# DRV8701ESheet.net
KiCad netlist of a schematic drawn in Altium Designer
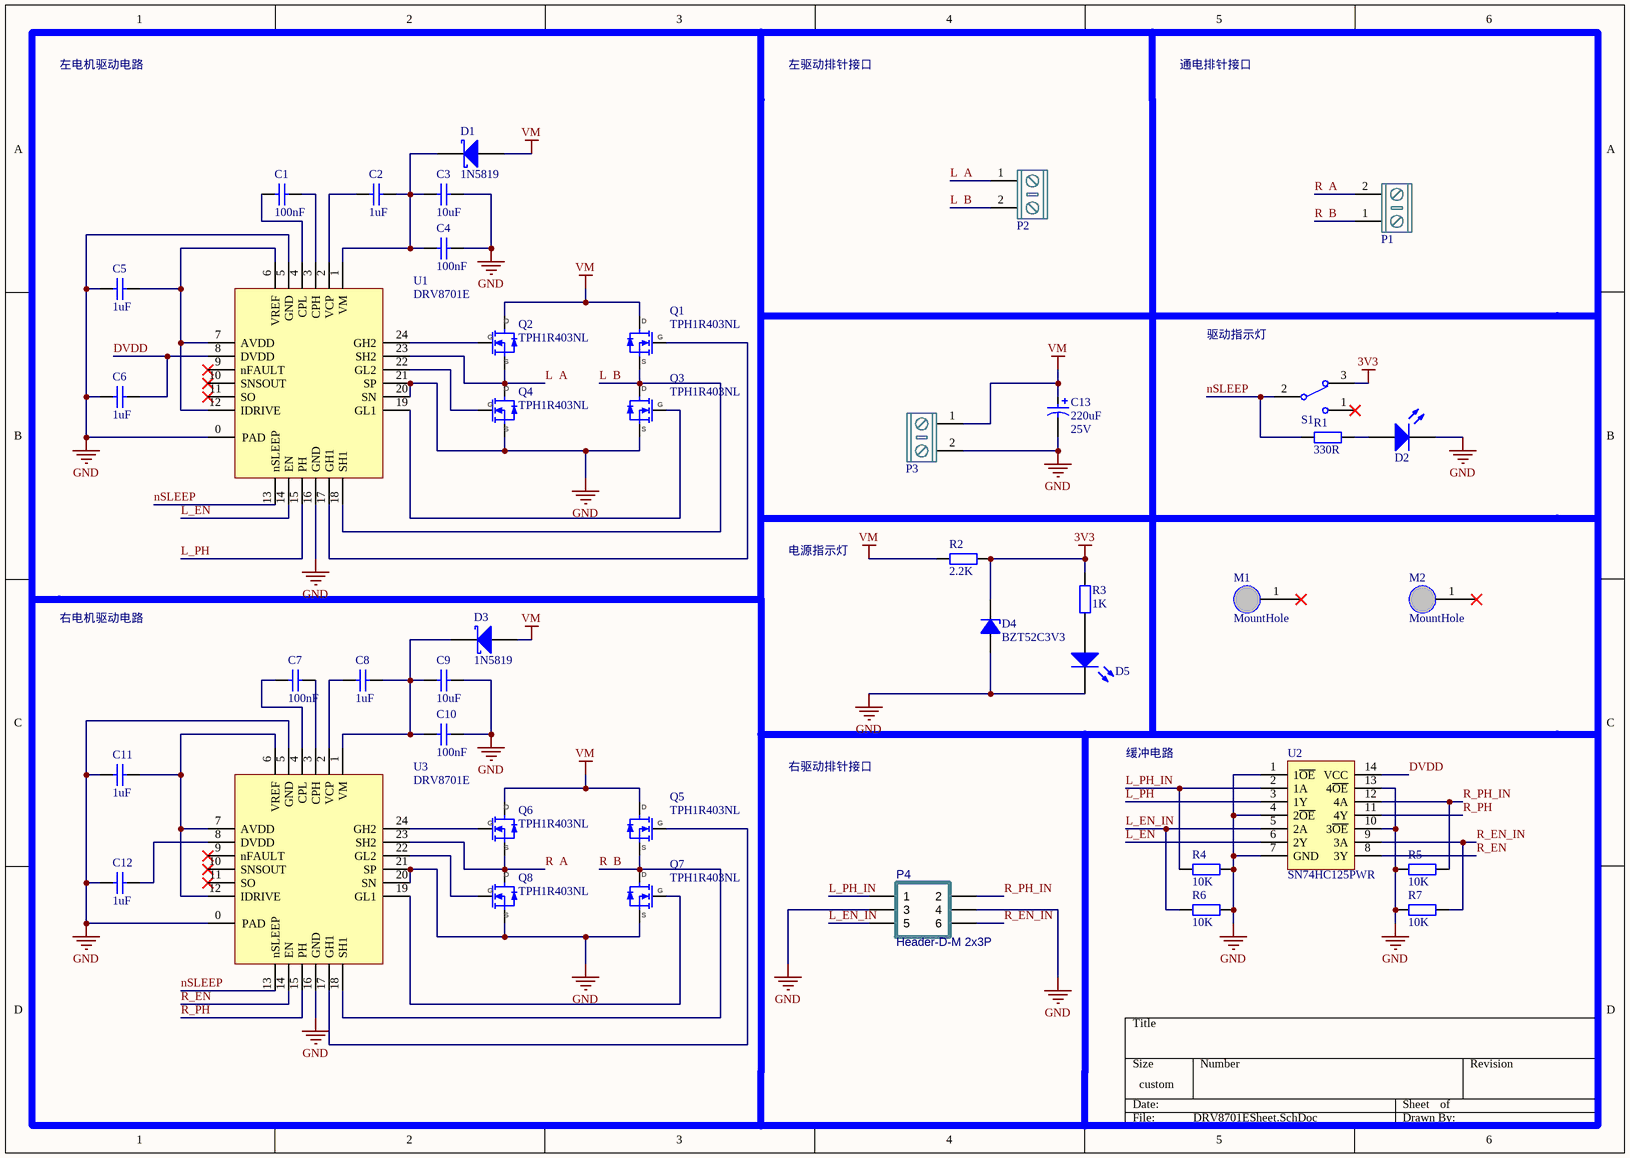
[diagram p0: DRV8701ESheet.SchDoc]

(export (version "E")
  (design (tool "Eeschema 10.0.6"))
  (components
    (comp (ref "C1")
      (value "100nF")
      (footprint "C0603_L")
      (description "贴片电容")
      (libsource (lib "0.1_电容&电感&电阻&保险丝") (part "C-SMD"))
    )
    (comp (ref "C2")
      (value "1uF")
      (footprint "C0603_L")
      (description "贴片电容")
      (libsource (lib "0.1_电容&电感&电阻&保险丝") (part "C-SMD"))
    )
    (comp (ref "C3")
      (value "10uF")
      (footprint "C0603_L")
      (description "贴片电容")
      (libsource (lib "0.1_电容&电感&电阻&保险丝") (part "C-SMD"))
    )
    (comp (ref "C4")
      (value "100nF")
      (footprint "C0603_L")
      (description "贴片电容")
      (libsource (lib "0.1_电容&电感&电阻&保险丝") (part "C-SMD"))
    )
    (comp (ref "C5")
      (value "1uF")
      (footprint "C0603_L")
      (description "贴片电容")
      (libsource (lib "0.1_电容&电感&电阻&保险丝") (part "C-SMD"))
    )
    (comp (ref "C6")
      (value "1uF")
      (footprint "C0603_L")
      (description "贴片电容")
      (libsource (lib "0.1_电容&电感&电阻&保险丝") (part "C-SMD"))
    )
    (comp (ref "C7")
      (value "100nF")
      (footprint "C0603_L")
      (description "贴片电容")
      (libsource (lib "0.1_电容&电感&电阻&保险丝") (part "C-SMD"))
    )
    (comp (ref "C8")
      (value "1uF")
      (footprint "C0603_L")
      (description "贴片电容")
      (libsource (lib "0.1_电容&电感&电阻&保险丝") (part "C-SMD"))
    )
    (comp (ref "C9")
      (value "10uF")
      (footprint "C0603_L")
      (description "贴片电容")
      (libsource (lib "0.1_电容&电感&电阻&保险丝") (part "C-SMD"))
    )
    (comp (ref "C10")
      (value "100nF")
      (footprint "C0603_L")
      (description "贴片电容")
      (libsource (lib "0.1_电容&电感&电阻&保险丝") (part "C-SMD"))
    )
    (comp (ref "C11")
      (value "1uF")
      (footprint "C0603_L")
      (description "贴片电容")
      (libsource (lib "0.1_电容&电感&电阻&保险丝") (part "C-SMD"))
    )
    (comp (ref "C12")
      (value "1uF")
      (footprint "C0603_L")
      (description "贴片电容")
      (libsource (lib "0.1_电容&电感&电阻&保险丝") (part "C-SMD"))
    )
    (comp (ref "C13")
      (value "220uF")
      (footprint "CAPPR3.5-8X11.5")
      (description "Polarized Capacitor (Radial)")
      (fields
        (field (name "VOLTAGE") "25V")
        (field (name "Comment") "220uF 25V")
        (field (name "PUBLISHER") "Altium Limited")
      )
      (libsource (lib "DRV8701E 双驱V1.1 集成封装库") (part "Cap-Elect"))
    )
    (comp (ref "D1")
      (value "1N5819")
      (footprint "SOD-323")
      (description "肖特基二极管")
      (libsource (lib "0.2_二极管&整流桥") (part "1N5819"))
    )
    (comp (ref "D2")
      (value "LED")
      (footprint "LED-0603_R")
      (description "贴片发光二极管")
      (libsource (lib "0.3_LED发光二极管") (part "LED_SMD"))
    )
    (comp (ref "D3")
      (value "1N5819")
      (footprint "SOD-323")
      (description "肖特基二极管")
      (libsource (lib "0.2_二极管&整流桥") (part "1N5819"))
    )
    (comp (ref "D4")
      (value "BZT52C3V3")
      (footprint "SOD-123-L")
      (description "3.3V稳压二极管")
      (fields (field (name "PUBLISHER") "Altium Limited"))
      (libsource (lib "智能车驱动板DRV8701E") (part "Diode Zen"))
    )
    (comp (ref "D5")
      (value "LED")
      (footprint "LED-0603_R")
      (description "贴片发光二极管")
      (libsource (lib "智能车驱动板DRV8701E") (part "LED_SMD"))
    )
    (comp (ref "M1")
      (value "MountHole")
      (footprint "M3-MountSlot")
      (description "固定孔")
      (libsource (lib "DRV8701E 双驱V1.1 集成封装库") (part "MountHole"))
    )
    (comp (ref "M2")
      (value "MountHole")
      (footprint "M3-MountSlot")
      (description "固定孔")
      (libsource (lib "DRV8701E 双驱V1.1 集成封装库") (part "MountHole"))
    )
    (comp (ref "P1")
      (value "KF/WJ/DG 30x connecter")
      (footprint "XT30-M")
      (description "接线端子 2Pin")
      (libsource (lib "RT1064_V1主板器件封装集成库") (part "KF/WJ/DG 30x"))
    )
    (comp (ref "P2")
      (value "KF/WJ/DG 30x connecter")
      (footprint "XT30-M")
      (description "接线端子 2Pin")
      (libsource (lib "RT1064_V1主板器件封装集成库") (part "KF/WJ/DG 30x"))
    )
    (comp (ref "P3")
      (value "KF/WJ/DG 30x connecter")
      (footprint "KF/WJ/DG 301-2p-5.0mm")
      (description "接线端子 2Pin")
      (libsource (lib "RT1064_V1主板器件封装集成库") (part "KF/WJ/DG 30x"))
    )
    (comp (ref "P4")
      (value "Header-D-M 2x3P")
      (footprint "HDR2X3-M-SMT")
      (description "2x3pin, 贴片, 双排针")
      (libsource (lib "RT1064_V1主板器件封装集成库") (part "Header-S-M 2x3P"))
    )
    (comp (ref "Q1")
      (value "TPH1R403NL")
      (footprint "DFN5x6")
      (description "N沟道MOS")
      (libsource (lib "0.4_场效应管&可控硅") (part "TPH1R403NL"))
    )
    (comp (ref "Q2")
      (value "TPH1R403NL")
      (footprint "DFN5x6")
      (description "N沟道MOS")
      (libsource (lib "0.4_场效应管&可控硅") (part "TPH1R403NL"))
    )
    (comp (ref "Q3")
      (value "TPH1R403NL")
      (footprint "DFN5x6")
      (description "N沟道MOS")
      (libsource (lib "0.4_场效应管&可控硅") (part "TPH1R403NL"))
    )
    (comp (ref "Q4")
      (value "TPH1R403NL")
      (footprint "DFN5x6")
      (description "N沟道MOS")
      (libsource (lib "0.4_场效应管&可控硅") (part "TPH1R403NL"))
    )
    (comp (ref "Q5")
      (value "TPH1R403NL")
      (footprint "DFN5x6")
      (description "N沟道MOS")
      (libsource (lib "0.4_场效应管&可控硅") (part "TPH1R403NL"))
    )
    (comp (ref "Q6")
      (value "TPH1R403NL")
      (footprint "DFN5x6")
      (description "N沟道MOS")
      (libsource (lib "0.4_场效应管&可控硅") (part "TPH1R403NL"))
    )
    (comp (ref "Q7")
      (value "TPH1R403NL")
      (footprint "DFN5x6")
      (description "N沟道MOS")
      (libsource (lib "0.4_场效应管&可控硅") (part "TPH1R403NL"))
    )
    (comp (ref "Q8")
      (value "TPH1R403NL")
      (footprint "DFN5x6")
      (description "N沟道MOS")
      (libsource (lib "0.4_场效应管&可控硅") (part "TPH1R403NL"))
    )
    (comp (ref "R1")
      (value "330R")
      (footprint "R0603_L")
      (description "贴片电阻")
      (libsource (lib "0.1_电容&电感&电阻&保险丝") (part "R-SMD"))
    )
    (comp (ref "R2")
      (value "2.2K")
      (footprint "R0603_L")
      (description "贴片电阻")
      (libsource (lib "0.1_电容&电感&电阻&保险丝") (part "R-SMD"))
    )
    (comp (ref "R3")
      (value "1K")
      (footprint "R0603_L")
      (description "贴片电阻")
      (libsource (lib "智能车驱动板DRV8701E") (part "R-SMD"))
    )
    (comp (ref "R4")
      (value "10K")
      (footprint "R0603_L")
      (description "贴片电阻")
      (libsource (lib "0.1_电容&电感&电阻&保险丝") (part "R-SMD"))
    )
    (comp (ref "R5")
      (value "10K")
      (footprint "R0603_L")
      (description "贴片电阻")
      (libsource (lib "0.1_电容&电感&电阻&保险丝") (part "R-SMD"))
    )
    (comp (ref "R6")
      (value "10K")
      (footprint "R0603_L")
      (description "贴片电阻")
      (libsource (lib "0.1_电容&电感&电阻&保险丝") (part "R-SMD"))
    )
    (comp (ref "R7")
      (value "10K")
      (footprint "R0603_L")
      (description "贴片电阻")
      (libsource (lib "0.1_电容&电感&电阻&保险丝") (part "R-SMD"))
    )
    (comp (ref "S1")
      (value "SW-SPDT")
      (footprint "SS-12F23")
      (description "单刀双掷开关 3脚船型、钮子、拨动开关 SPDT Subminiature Toggle Switch")
      (fields (field (name "PUBLISHER") "Altium Limited"))
      (libsource (lib "RT1064_V1主板器件封装集成库") (part "SW-SPDT"))
    )
    (comp (ref "U1")
      (value "DRV8701E")
      (footprint "QFN24-4x4")
      (description "DRV8701E Ti全桥驱动芯片")
      (libsource (lib "智能车驱动板DRV8701E") (part "DRV8701E"))
    )
    (comp (ref "U2")
      (value "SN74HC125PWR")
      (footprint "TSSOP14")
      (description "三态输出的四路缓冲器")
      (libsource (lib "智能车驱动板DRV8701E") (part "SN74HC125PWR"))
    )
    (comp (ref "U3")
      (value "DRV8701E")
      (footprint "QFN24-4x4")
      (description "DRV8701E Ti全桥驱动芯片")
      (libsource (lib "智能车驱动板DRV8701E") (part "DRV8701E"))
    )
  )
  (nets
    (net (code "1") (name "/DVDD") (class "Default")
      (node (ref "C6") (pin "2") (pinfunction "2_2") (pintype "passive"))
      (node (ref "U1") (pin "8") (pinfunction "DVDD_8") (pintype "passive"))
      (node (ref "U2") (pin "14") (pinfunction "VCC_14") (pintype "passive"))
    )
    (net (code "2") (name "/L  A") (class "Default")
      (node (ref "P2") (pin "1") (pinfunction "1_1") (pintype "passive"))
      (node (ref "Q2") (pin "3") (pinfunction "S_3") (pintype "passive"))
      (node (ref "Q4") (pin "1") (pinfunction "D_1") (pintype "passive"))
      (node (ref "U1") (pin "23") (pinfunction "SH2_23") (pintype "passive"))
    )
    (net (code "3") (name "/L  B") (class "Default")
      (node (ref "P2") (pin "2") (pinfunction "2_2") (pintype "passive"))
      (node (ref "Q1") (pin "3") (pinfunction "S_3") (pintype "passive"))
      (node (ref "Q3") (pin "1") (pinfunction "D_1") (pintype "passive"))
      (node (ref "U1") (pin "18") (pinfunction "SH1_18") (pintype "passive"))
    )
    (net (code "4") (name "/L_EN") (class "Default")
      (node (ref "U1") (pin "14") (pinfunction "EN_14") (pintype "passive"))
      (node (ref "U2") (pin "6") (pinfunction "2Y_6") (pintype "passive"))
    )
    (net (code "5") (name "/L_EN_IN") (class "Default")
      (node (ref "P4") (pin "5") (pinfunction "5_5") (pintype "passive"))
      (node (ref "R6") (pin "1") (pinfunction "1_1") (pintype "passive"))
      (node (ref "U2") (pin "5") (pinfunction "2A_5") (pintype "passive"))
    )
    (net (code "6") (name "/L_PH") (class "Default")
      (node (ref "U1") (pin "15") (pinfunction "PH_15") (pintype "passive"))
      (node (ref "U2") (pin "3") (pinfunction "1Y_3") (pintype "passive"))
    )
    (net (code "7") (name "/L_PH_IN") (class "Default")
      (node (ref "P4") (pin "1") (pinfunction "1_1") (pintype "passive"))
      (node (ref "R4") (pin "1") (pinfunction "1_1") (pintype "passive"))
      (node (ref "U2") (pin "2") (pinfunction "1A_2") (pintype "passive"))
    )
    (net (code "8") (name "/R  A") (class "Default")
      (node (ref "P1") (pin "2") (pinfunction "2_2") (pintype "passive"))
      (node (ref "Q6") (pin "3") (pinfunction "S_3") (pintype "passive"))
      (node (ref "Q8") (pin "1") (pinfunction "D_1") (pintype "passive"))
      (node (ref "U3") (pin "23") (pinfunction "SH2_23") (pintype "passive"))
    )
    (net (code "9") (name "/R  B") (class "Default")
      (node (ref "P1") (pin "1") (pinfunction "1_1") (pintype "passive"))
      (node (ref "Q5") (pin "3") (pinfunction "S_3") (pintype "passive"))
      (node (ref "Q7") (pin "1") (pinfunction "D_1") (pintype "passive"))
      (node (ref "U3") (pin "18") (pinfunction "SH1_18") (pintype "passive"))
    )
    (net (code "10") (name "/R_EN") (class "Default")
      (node (ref "U2") (pin "8") (pinfunction "3Y_8") (pintype "passive"))
      (node (ref "U3") (pin "14") (pinfunction "EN_14") (pintype "passive"))
    )
    (net (code "11") (name "/R_EN_IN") (class "Default")
      (node (ref "P4") (pin "6") (pinfunction "6_6") (pintype "passive"))
      (node (ref "R7") (pin "2") (pinfunction "2_2") (pintype "passive"))
      (node (ref "U2") (pin "9") (pinfunction "3A_9") (pintype "passive"))
    )
    (net (code "12") (name "/R_PH") (class "Default")
      (node (ref "U2") (pin "11") (pinfunction "4Y_11") (pintype "passive"))
      (node (ref "U3") (pin "15") (pinfunction "PH_15") (pintype "passive"))
    )
    (net (code "13") (name "/R_PH_IN") (class "Default")
      (node (ref "P4") (pin "2") (pinfunction "2_2") (pintype "passive"))
      (node (ref "R5") (pin "2") (pinfunction "2_2") (pintype "passive"))
      (node (ref "U2") (pin "12") (pinfunction "4A_12") (pintype "passive"))
    )
    (net (code "14") (name "/nSLEEP") (class "Default")
      (node (ref "R1") (pin "1") (pinfunction "1_1") (pintype "passive"))
      (node (ref "S1") (pin "2") (pintype "passive"))
      (node (ref "U1") (pin "13") (pinfunction "nSLEEP_13") (pintype "passive"))
      (node (ref "U3") (pin "13") (pinfunction "nSLEEP_13") (pintype "passive"))
    )
    (net (code "15") (name "3V3") (class "Default")
      (node (ref "D4") (pin "K") (pinfunction "K_K") (pintype "passive"))
      (node (ref "R2") (pin "2") (pinfunction "2_2") (pintype "passive"))
      (node (ref "R3") (pin "2") (pinfunction "2_2") (pintype "passive"))
      (node (ref "S1") (pin "3") (pintype "passive"))
    )
    (net (code "16") (name "GND") (class "Default")
      (node (ref "C10") (pin "2") (pinfunction "2_2") (pintype "passive"))
      (node (ref "C11") (pin "1") (pinfunction "1_1") (pintype "passive"))
      (node (ref "C12") (pin "1") (pinfunction "1_1") (pintype "passive"))
      (node (ref "C13") (pin "2") (pinfunction "2_2") (pintype "passive"))
      (node (ref "C3") (pin "2") (pinfunction "2_2") (pintype "passive"))
      (node (ref "C4") (pin "2") (pinfunction "2_2") (pintype "passive"))
      (node (ref "C5") (pin "1") (pinfunction "1_1") (pintype "passive"))
      (node (ref "C6") (pin "1") (pinfunction "1_1") (pintype "passive"))
      (node (ref "C9") (pin "2") (pinfunction "2_2") (pintype "passive"))
      (node (ref "D2") (pin "2") (pinfunction "K_2") (pintype "passive"))
      (node (ref "D4") (pin "A") (pinfunction "A_A") (pintype "passive"))
      (node (ref "D5") (pin "2") (pinfunction "K_2") (pintype "passive"))
      (node (ref "P3") (pin "2") (pinfunction "2_2") (pintype "passive"))
      (node (ref "P4") (pin "3") (pinfunction "3_3") (pintype "passive"))
      (node (ref "P4") (pin "4") (pinfunction "4_4") (pintype "passive"))
      (node (ref "Q3") (pin "3") (pinfunction "S_3") (pintype "passive"))
      (node (ref "Q4") (pin "3") (pinfunction "S_3") (pintype "passive"))
      (node (ref "Q7") (pin "3") (pinfunction "S_3") (pintype "passive"))
      (node (ref "Q8") (pin "3") (pinfunction "S_3") (pintype "passive"))
      (node (ref "R4") (pin "2") (pinfunction "2_2") (pintype "passive"))
      (node (ref "R5") (pin "1") (pinfunction "1_1") (pintype "passive"))
      (node (ref "R6") (pin "2") (pinfunction "2_2") (pintype "passive"))
      (node (ref "R7") (pin "1") (pinfunction "1_1") (pintype "passive"))
      (node (ref "U1") (pin "0") (pinfunction "PAD_0") (pintype "passive"))
      (node (ref "U1") (pin "16") (pinfunction "GND_16") (pintype "passive"))
      (node (ref "U1") (pin "20") (pinfunction "SN_20") (pintype "passive"))
      (node (ref "U1") (pin "21") (pinfunction "SP_21") (pintype "passive"))
      (node (ref "U1") (pin "5") (pinfunction "GND_5") (pintype "passive"))
      (node (ref "U2") (pin "1") (pinfunction "1~{OE}_1") (pintype "passive"))
      (node (ref "U2") (pin "10") (pinfunction "3~{OE}_10") (pintype "passive"))
      (node (ref "U2") (pin "13") (pinfunction "4~{OE}_13") (pintype "passive"))
      (node (ref "U2") (pin "4") (pinfunction "2~{OE}_4") (pintype "passive"))
      (node (ref "U2") (pin "7") (pinfunction "GND_7") (pintype "passive"))
      (node (ref "U3") (pin "0") (pinfunction "PAD_0") (pintype "passive"))
      (node (ref "U3") (pin "16") (pinfunction "GND_16") (pintype "passive"))
      (node (ref "U3") (pin "20") (pinfunction "SN_20") (pintype "passive"))
      (node (ref "U3") (pin "21") (pinfunction "SP_21") (pintype "passive"))
      (node (ref "U3") (pin "5") (pinfunction "GND_5") (pintype "passive"))
    )
    (net (code "17") (name "Net-(D1-K)") (class "Default")
      (node (ref "C2") (pin "2") (pinfunction "2_2") (pintype "passive"))
      (node (ref "C3") (pin "1") (pinfunction "1_1") (pintype "passive"))
      (node (ref "C4") (pin "1") (pinfunction "1_1") (pintype "passive"))
      (node (ref "D1") (pin "2") (pinfunction "K_2") (pintype "passive"))
      (node (ref "U1") (pin "1") (pinfunction "VM_1") (pintype "passive"))
    )
    (net (code "18") (name "Net-(D2-A)") (class "Default")
      (node (ref "D2") (pin "1") (pinfunction "A_1") (pintype "passive"))
      (node (ref "R1") (pin "2") (pinfunction "2_2") (pintype "passive"))
    )
    (net (code "19") (name "Net-(D3-K)") (class "Default")
      (node (ref "C10") (pin "1") (pinfunction "1_1") (pintype "passive"))
      (node (ref "C8") (pin "2") (pinfunction "2_2") (pintype "passive"))
      (node (ref "C9") (pin "1") (pinfunction "1_1") (pintype "passive"))
      (node (ref "D3") (pin "2") (pinfunction "K_2") (pintype "passive"))
      (node (ref "U3") (pin "1") (pinfunction "VM_1") (pintype "passive"))
    )
    (net (code "20") (name "Net-(D5-A)") (class "Default")
      (node (ref "D5") (pin "1") (pinfunction "A_1") (pintype "passive"))
      (node (ref "R3") (pin "1") (pinfunction "1_1") (pintype "passive"))
    )
    (net (code "21") (name "Net-(Q1-G)") (class "Default")
      (node (ref "Q1") (pin "2") (pinfunction "G_2") (pintype "passive"))
      (node (ref "U1") (pin "17") (pinfunction "GH1_17") (pintype "passive"))
    )
    (net (code "22") (name "Net-(Q2-G)") (class "Default")
      (node (ref "Q2") (pin "2") (pinfunction "G_2") (pintype "passive"))
      (node (ref "U1") (pin "24") (pinfunction "GH2_24") (pintype "passive"))
    )
    (net (code "23") (name "Net-(Q3-G)") (class "Default")
      (node (ref "Q3") (pin "2") (pinfunction "G_2") (pintype "passive"))
      (node (ref "U1") (pin "19") (pinfunction "GL1_19") (pintype "passive"))
    )
    (net (code "24") (name "Net-(Q4-G)") (class "Default")
      (node (ref "Q4") (pin "2") (pinfunction "G_2") (pintype "passive"))
      (node (ref "U1") (pin "22") (pinfunction "GL2_22") (pintype "passive"))
    )
    (net (code "25") (name "Net-(Q5-G)") (class "Default")
      (node (ref "Q5") (pin "2") (pinfunction "G_2") (pintype "passive"))
      (node (ref "U3") (pin "17") (pinfunction "GH1_17") (pintype "passive"))
    )
    (net (code "26") (name "Net-(Q6-G)") (class "Default")
      (node (ref "Q6") (pin "2") (pinfunction "G_2") (pintype "passive"))
      (node (ref "U3") (pin "24") (pinfunction "GH2_24") (pintype "passive"))
    )
    (net (code "27") (name "Net-(Q7-G)") (class "Default")
      (node (ref "Q7") (pin "2") (pinfunction "G_2") (pintype "passive"))
      (node (ref "U3") (pin "19") (pinfunction "GL1_19") (pintype "passive"))
    )
    (net (code "28") (name "Net-(Q8-G)") (class "Default")
      (node (ref "Q8") (pin "2") (pinfunction "G_2") (pintype "passive"))
      (node (ref "U3") (pin "22") (pinfunction "GL2_22") (pintype "passive"))
    )
    (net (code "29") (name "Net-(U1-AVDD)") (class "Default")
      (node (ref "C5") (pin "2") (pinfunction "2_2") (pintype "passive"))
      (node (ref "U1") (pin "12") (pinfunction "IDRIVE_12") (pintype "passive"))
      (node (ref "U1") (pin "6") (pinfunction "VREF_6") (pintype "passive"))
      (node (ref "U1") (pin "7") (pinfunction "AVDD_7") (pintype "passive"))
    )
    (net (code "30") (name "Net-(U1-CPH)") (class "Default")
      (node (ref "C1") (pin "2") (pinfunction "2_2") (pintype "passive"))
      (node (ref "U1") (pin "3") (pinfunction "CPH_3") (pintype "passive"))
    )
    (net (code "31") (name "Net-(U1-CPL)") (class "Default")
      (node (ref "C1") (pin "1") (pinfunction "1_1") (pintype "passive"))
      (node (ref "U1") (pin "4") (pinfunction "CPL_4") (pintype "passive"))
    )
    (net (code "32") (name "Net-(U1-VCP)") (class "Default")
      (node (ref "C2") (pin "1") (pinfunction "1_1") (pintype "passive"))
      (node (ref "U1") (pin "2") (pinfunction "VCP_2") (pintype "passive"))
    )
    (net (code "33") (name "Net-(U3-AVDD)") (class "Default")
      (node (ref "C11") (pin "2") (pinfunction "2_2") (pintype "passive"))
      (node (ref "U3") (pin "12") (pinfunction "IDRIVE_12") (pintype "passive"))
      (node (ref "U3") (pin "6") (pinfunction "VREF_6") (pintype "passive"))
      (node (ref "U3") (pin "7") (pinfunction "AVDD_7") (pintype "passive"))
    )
    (net (code "34") (name "Net-(U3-CPH)") (class "Default")
      (node (ref "C7") (pin "2") (pinfunction "2_2") (pintype "passive"))
      (node (ref "U3") (pin "3") (pinfunction "CPH_3") (pintype "passive"))
    )
    (net (code "35") (name "Net-(U3-CPL)") (class "Default")
      (node (ref "C7") (pin "1") (pinfunction "1_1") (pintype "passive"))
      (node (ref "U3") (pin "4") (pinfunction "CPL_4") (pintype "passive"))
    )
    (net (code "36") (name "Net-(U3-DVDD)") (class "Default")
      (node (ref "C12") (pin "2") (pinfunction "2_2") (pintype "passive"))
      (node (ref "U3") (pin "8") (pinfunction "DVDD_8") (pintype "passive"))
    )
    (net (code "37") (name "Net-(U3-VCP)") (class "Default")
      (node (ref "C8") (pin "1") (pinfunction "1_1") (pintype "passive"))
      (node (ref "U3") (pin "2") (pinfunction "VCP_2") (pintype "passive"))
    )
    (net (code "38") (name "VM") (class "Default")
      (node (ref "C13") (pin "1") (pinfunction "1_1") (pintype "passive"))
      (node (ref "D1") (pin "1") (pinfunction "A_1") (pintype "passive"))
      (node (ref "D3") (pin "1") (pinfunction "A_1") (pintype "passive"))
      (node (ref "P3") (pin "1") (pinfunction "1_1") (pintype "passive"))
      (node (ref "Q1") (pin "1") (pinfunction "D_1") (pintype "passive"))
      (node (ref "Q2") (pin "1") (pinfunction "D_1") (pintype "passive"))
      (node (ref "Q5") (pin "1") (pinfunction "D_1") (pintype "passive"))
      (node (ref "Q6") (pin "1") (pinfunction "D_1") (pintype "passive"))
      (node (ref "R2") (pin "1") (pinfunction "1_1") (pintype "passive"))
    )
    (net (code "39") (name "unconnected-(M1-Pad1)") (class "Default")
      (node (ref "M1") (pin "1") (pinfunction "1_1") (pintype "passive+no_connect"))
    )
    (net (code "40") (name "unconnected-(M2-Pad1)") (class "Default")
      (node (ref "M2") (pin "1") (pinfunction "1_1") (pintype "passive+no_connect"))
    )
    (net (code "41") (name "unconnected-(S1-Pad1)") (class "Default")
      (node (ref "S1") (pin "1") (pintype "passive+no_connect"))
    )
    (net (code "42") (name "unconnected-(U1-SNSOUT-Pad10)") (class "Default")
      (node (ref "U1") (pin "10") (pinfunction "SNSOUT_10") (pintype "passive+no_connect"))
    )
    (net (code "43") (name "unconnected-(U1-SO-Pad11)") (class "Default")
      (node (ref "U1") (pin "11") (pinfunction "SO_11") (pintype "passive+no_connect"))
    )
    (net (code "44") (name "unconnected-(U1-nFAULT-Pad9)") (class "Default")
      (node (ref "U1") (pin "9") (pinfunction "nFAULT_9") (pintype "passive+no_connect"))
    )
    (net (code "45") (name "unconnected-(U3-SNSOUT-Pad10)") (class "Default")
      (node (ref "U3") (pin "10") (pinfunction "SNSOUT_10") (pintype "passive+no_connect"))
    )
    (net (code "46") (name "unconnected-(U3-SO-Pad11)") (class "Default")
      (node (ref "U3") (pin "11") (pinfunction "SO_11") (pintype "passive+no_connect"))
    )
    (net (code "47") (name "unconnected-(U3-nFAULT-Pad9)") (class "Default")
      (node (ref "U3") (pin "9") (pinfunction "nFAULT_9") (pintype "passive+no_connect"))
    )
  )
)
